# top.net
KiCad netlist of a schematic drawn in Altium Designer
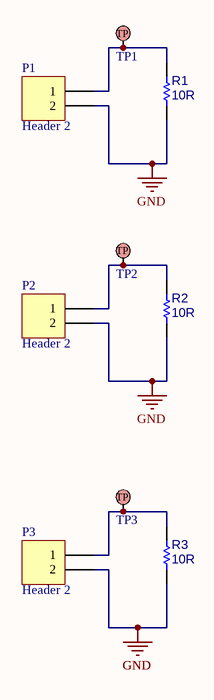
[diagram p0: top.SchDoc]

(export (version "E")
  (design (tool "Eeschema 10.0.6"))
  (components
    (comp (ref "P1")
      (value "Header 2")
      (footprint "HDR1X2")
      (description "Header, 2-Pin")
      (fields (field (name "PUBLISHER") "Altium Limited"))
      (libsource (lib "Miscellaneous Connectors") (part "Header 2"))
    )
    (comp (ref "P2")
      (value "Header 2")
      (footprint "HDR1X2")
      (description "Header, 2-Pin")
      (fields (field (name "PUBLISHER") "Altium Limited"))
      (libsource (lib "Miscellaneous Connectors") (part "Header 2"))
    )
    (comp (ref "P3")
      (value "Header 2")
      (footprint "HDR1X2")
      (description "Header, 2-Pin")
      (fields (field (name "PUBLISHER") "Altium Limited"))
      (libsource (lib "Miscellaneous Connectors") (part "Header 2"))
    )
    (comp (ref "R1")
      (value "10R")
      (footprint "0805[2012]")
      (description "Resistor")
      (libsource (lib "SymbolsStd") (part "Res"))
    )
    (comp (ref "R2")
      (value "10R")
      (footprint "0805[2012]")
      (description "Resistor")
      (libsource (lib "SymbolsStd") (part "Res"))
    )
    (comp (ref "R3")
      (value "10R")
      (footprint "0805[2012]")
      (description "Resistor")
      (libsource (lib "SymbolsStd") (part "Res"))
    )
    (comp (ref "TP1")
      (value "Single Pin Test Point")
      (footprint "testpoint_SMD")
      (libsource (lib "SymbolsStd") (part "Testpoint"))
    )
    (comp (ref "TP2")
      (value "Single Pin Test Point")
      (footprint "testpoint_SMD")
      (libsource (lib "SymbolsStd") (part "Testpoint"))
    )
    (comp (ref "TP3")
      (value "Single Pin Test Point")
      (footprint "testpoint_SMD")
      (libsource (lib "SymbolsStd") (part "Testpoint"))
    )
  )
  (nets
    (net (code "1") (name "GND") (class "Default")
      (node (ref "P1") (pin "2") (pinfunction "2_2") (pintype "passive"))
      (node (ref "P2") (pin "2") (pinfunction "2_2") (pintype "passive"))
      (node (ref "P3") (pin "2") (pinfunction "2_2") (pintype "passive"))
      (node (ref "R1") (pin "1") (pinfunction "1_1") (pintype "passive"))
      (node (ref "R2") (pin "1") (pinfunction "1_1") (pintype "passive"))
      (node (ref "R3") (pin "1") (pinfunction "1_1") (pintype "passive"))
    )
    (net (code "2") (name "Net-(P1-Pad1)") (class "Default")
      (node (ref "P1") (pin "1") (pinfunction "1_1") (pintype "passive"))
      (node (ref "R1") (pin "2") (pinfunction "2_2") (pintype "passive"))
      (node (ref "TP1") (pin "0") (pinfunction "0_0") (pintype "passive"))
    )
    (net (code "3") (name "Net-(P2-Pad1)") (class "Default")
      (node (ref "P2") (pin "1") (pinfunction "1_1") (pintype "passive"))
      (node (ref "R2") (pin "2") (pinfunction "2_2") (pintype "passive"))
      (node (ref "TP2") (pin "0") (pinfunction "0_0") (pintype "passive"))
    )
    (net (code "4") (name "Net-(P3-Pad1)") (class "Default")
      (node (ref "P3") (pin "1") (pinfunction "1_1") (pintype "passive"))
      (node (ref "R3") (pin "2") (pinfunction "2_2") (pintype "passive"))
      (node (ref "TP3") (pin "0") (pinfunction "0_0") (pintype "passive"))
    )
  )
)
